# JIG_TEST_AUX_PIXYO-V10A.net
KiCad netlist of a schematic drawn in Altium Designer
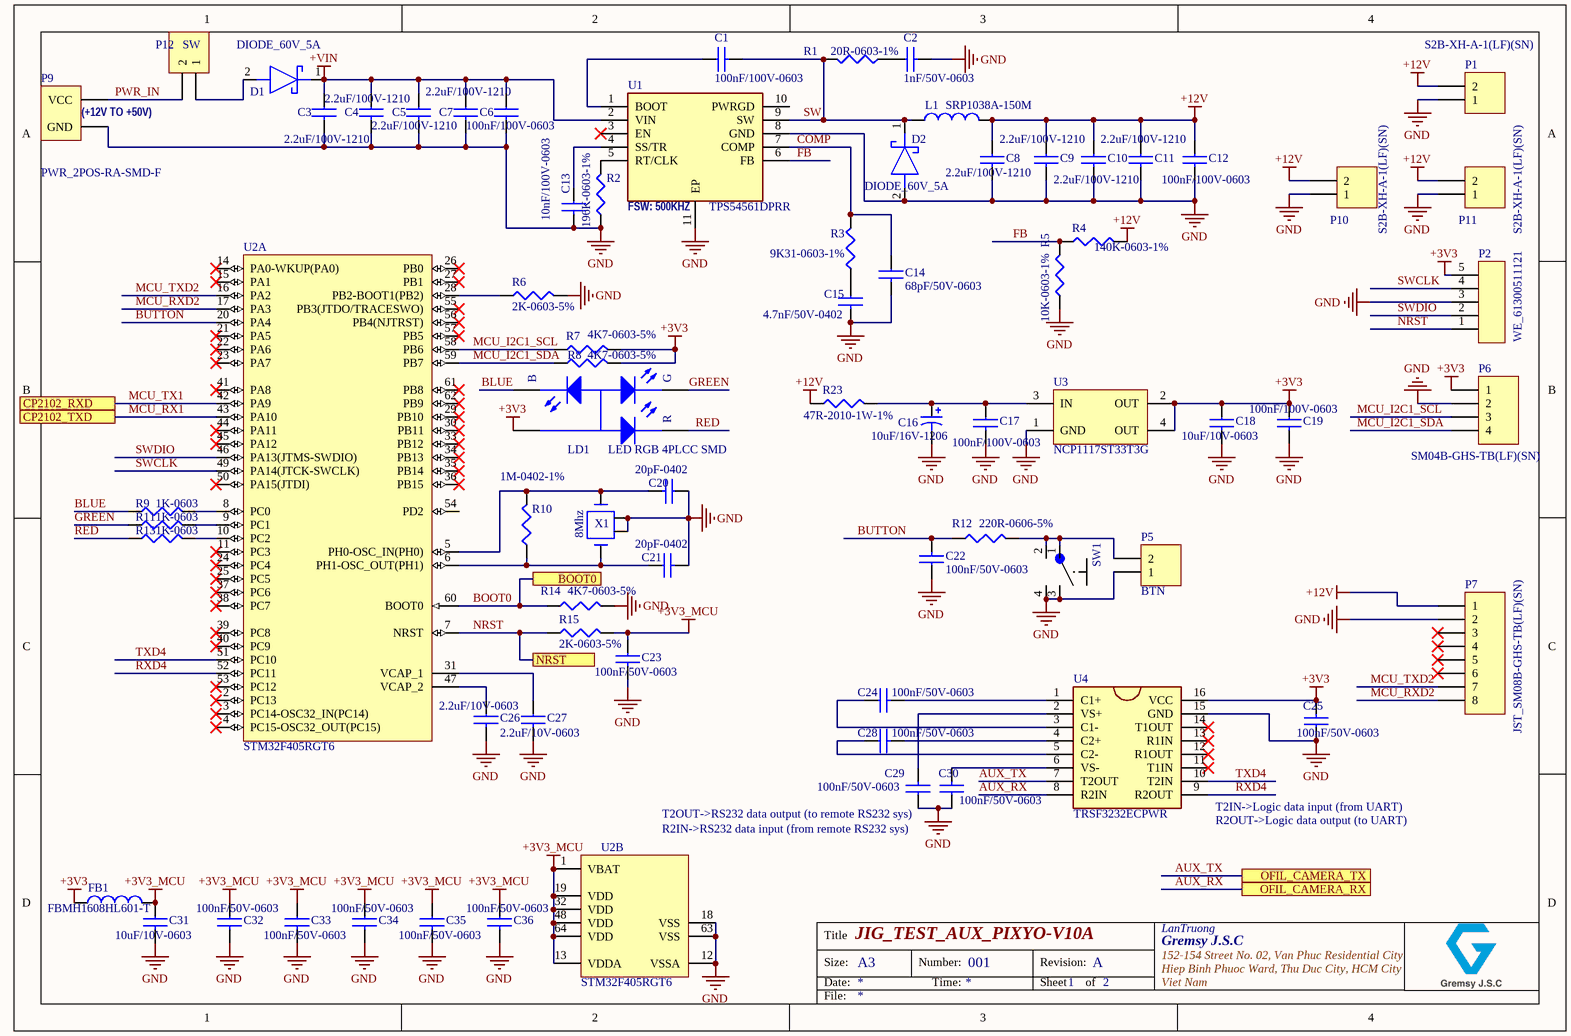
[diagram p0: JIG_TEST_AUX_PIXYO-V10A.SchDoc]

(export (version "E")
  (design (tool "Eeschema 10.0.6"))
  (components
    (comp (ref "C1")
      (value "100nF/100V-0603")
      (footprint "CAP0603")
      (description "CAP CER 0.1UF 100V X7R 0603")
      (fields (field (name "MANUFACTURER") "Yageo") (field (name "TOLERANCE") "±10%"))
      (libsource (lib "GremsyJSC") (part "CAP_100nF/100V-0603-10%"))
    )
    (comp (ref "C2")
      (value "1nF/50V-0603")
      (footprint "CAP0603")
      (description "CAP CER 1000PF 50V X7R 0603")
      (fields (field (name "MANUFACTURER") "Yageo") (field (name "TOLERANCE") "10%"))
      (libsource (lib "GremsyJSC") (part "CAP_1nF/50V-0603-10%"))
    )
    (comp (ref "C3")
      (value "2.2uF/100V-1210")
      (footprint "CAP1210")
      (description "CAP CER 2.2UF 100V X7R 1210")
      (fields (field (name "MANUFACTURER") "Taiyo Yuden") (field (name "TOLERANCE") "±10%"))
      (libsource (lib "GremsyJSC") (part "CAP_2.2uF/100V-1210-10%"))
    )
    (comp (ref "C4")
      (value "2.2uF/100V-1210")
      (footprint "CAP1210")
      (description "CAP CER 2.2UF 100V X7R 1210")
      (fields (field (name "MANUFACTURER") "Taiyo Yuden") (field (name "TOLERANCE") "±10%"))
      (libsource (lib "GremsyJSC") (part "CAP_2.2uF/100V-1210-10%"))
    )
    (comp (ref "C5")
      (value "2.2uF/100V-1210")
      (footprint "CAP1210")
      (description "CAP CER 2.2UF 100V X7R 1210")
      (fields (field (name "MANUFACTURER") "Taiyo Yuden") (field (name "TOLERANCE") "±10%"))
      (libsource (lib "GremsyJSC") (part "CAP_2.2uF/100V-1210-10%"))
    )
    (comp (ref "C6")
      (value "100nF/100V-0603")
      (footprint "CAP0603")
      (description "CAP CER 0.1UF 100V X7R 0603")
      (fields (field (name "MANUFACTURER") "Yageo") (field (name "TOLERANCE") "±10%"))
      (libsource (lib "GremsyJSC") (part "CAP_100nF/100V-0603-10%"))
    )
    (comp (ref "C7")
      (value "2.2uF/100V-1210")
      (footprint "CAP1210")
      (description "CAP CER 2.2UF 100V X7R 1210")
      (fields (field (name "MANUFACTURER") "Taiyo Yuden") (field (name "TOLERANCE") "±10%"))
      (libsource (lib "GremsyJSC") (part "CAP_2.2uF/100V-1210-10%"))
    )
    (comp (ref "C8")
      (value "2.2uF/100V-1210")
      (footprint "CAP1210")
      (description "CAP CER 2.2UF 100V X7R 1210")
      (fields (field (name "MANUFACTURER") "Taiyo Yuden") (field (name "TOLERANCE") "±10%"))
      (libsource (lib "GremsyJSC") (part "CAP_2.2uF/100V-1210-10%"))
    )
    (comp (ref "C9")
      (value "2.2uF/100V-1210")
      (footprint "CAP1210")
      (description "CAP CER 2.2UF 100V X7R 1210")
      (fields (field (name "MANUFACTURER") "Taiyo Yuden") (field (name "TOLERANCE") "±10%"))
      (libsource (lib "GremsyJSC") (part "CAP_2.2uF/100V-1210-10%"))
    )
    (comp (ref "C10")
      (value "2.2uF/100V-1210")
      (footprint "CAP1210")
      (description "CAP CER 2.2UF 100V X7R 1210")
      (fields (field (name "MANUFACTURER") "Taiyo Yuden") (field (name "TOLERANCE") "±10%"))
      (libsource (lib "GremsyJSC") (part "CAP_2.2uF/100V-1210-10%"))
    )
    (comp (ref "C11")
      (value "2.2uF/100V-1210")
      (footprint "CAP1210")
      (description "CAP CER 2.2UF 100V X7R 1210")
      (fields (field (name "MANUFACTURER") "Taiyo Yuden") (field (name "TOLERANCE") "±10%"))
      (libsource (lib "GremsyJSC") (part "CAP_2.2uF/100V-1210-10%"))
    )
    (comp (ref "C12")
      (value "100nF/100V-0603")
      (footprint "CAP0603")
      (description "CAP CER 0.1UF 100V X7R 0603")
      (fields (field (name "MANUFACTURER") "Yageo") (field (name "TOLERANCE") "±10%"))
      (libsource (lib "GremsyJSC") (part "CAP_100nF/100V-0603-10%"))
    )
    (comp (ref "C13")
      (value "10nF/100V-0603")
      (footprint "CAP0603")
      (description "CAP CER 10000PF 100V X7R 0603")
      (fields (field (name "MANUFACTURER") "Yageo") (field (name "TOLERANCE") "±10%"))
      (libsource (lib "GremsyJSC") (part "CAP_10nF/100V-0603-10%"))
    )
    (comp (ref "C14")
      (value "68pF/50V-0603")
      (footprint "CAP0603")
      (description "CAP CER 68PF 50V C0G/NPO 0603")
      (fields (field (name "MANUFACTURER") "Yageo") (field (name "TOLERANCE") "±5%"))
      (libsource (lib "GremsyJSC") (part "CAP_68pF/50V-0603-5%"))
    )
    (comp (ref "C15")
      (value "4.7nF/50V-0402")
      (footprint "CAP0402")
      (description "CAP CER 4700PF 50V X7R 0402")
      (fields (field (name "TOLERANCE") "5%"))
      (libsource (lib "GremsyJSC") (part "CAP_4.7nF/50V-0402-5%"))
    )
    (comp (ref "C16")
      (value "10uF/16V-1206")
      (footprint "CAP1206_TANTALUM_YELLOW")
      (description "CAP TANT 10UF 16V 10% 1206")
      (fields (field (name "TOLERANCE") "±10%"))
      (libsource (lib "GremsyJSC") (part "CAP_10uF/16V-1206-10%"))
    )
    (comp (ref "C17")
      (value "100nF/100V-0603")
      (footprint "CAP0603")
      (description "CAP CER 0.1UF 100V X7R 0603")
      (fields (field (name "MANUFACTURER") "Yageo") (field (name "TOLERANCE") "±10%"))
      (libsource (lib "GremsyJSC") (part "CAP_100nF/100V-0603-10%"))
    )
    (comp (ref "C18")
      (value "10uF/10V-0603")
      (footprint "CAP0603")
      (description "CAP CER 10UF 10V X5R 0603")
      (fields (field (name "TOLERANCE") "±10%"))
      (libsource (lib "GremsyJSC") (part "CAP_10uF/10V-0603-10%"))
    )
    (comp (ref "C19")
      (value "100nF/100V-0603")
      (footprint "CAP0603")
      (description "CAP CER 0.1UF 100V X7R 0603")
      (fields (field (name "MANUFACTURER") "Yageo") (field (name "TOLERANCE") "±10%"))
      (libsource (lib "GremsyJSC") (part "CAP_100nF/100V-0603-10%"))
    )
    (comp (ref "C20")
      (value "20pF-0402")
      (footprint "CAP0402")
      (description "CAP CER 20PF 50V C0G/NP0 0402")
      (fields (field (name "TOLERANCE") "1%"))
      (libsource (lib "GremsyJSC") (part "CAP_20pF/50V-0402-1%"))
    )
    (comp (ref "C21")
      (value "20pF-0402")
      (footprint "CAP0402")
      (description "CAP CER 20PF 50V C0G/NP0 0402")
      (fields (field (name "TOLERANCE") "1%"))
      (libsource (lib "GremsyJSC") (part "CAP_20pF/50V-0402-1%"))
    )
    (comp (ref "C22")
      (value "100nF/50V-0603")
      (footprint "CAP0603")
      (description "CAP CER 0.1UF 50V X7R 0603")
      (fields (field (name "TOLERANCE") "±10%"))
      (libsource (lib "GremsyJSC") (part "CAP_100nF/50V-0603-10%"))
    )
    (comp (ref "C23")
      (value "100nF/50V-0603")
      (footprint "CAP0603")
      (description "CAP CER 0.1UF 50V X7R 0603")
      (fields (field (name "TOLERANCE") "±10%"))
      (libsource (lib "GremsyJSC") (part "CAP_100nF/50V-0603-10%"))
    )
    (comp (ref "C24")
      (value "100nF/50V-0603")
      (footprint "CAP0603")
      (description "CAP CER 0.1UF 50V X7R 0603")
      (fields (field (name "TOLERANCE") "±10%"))
      (libsource (lib "GremsyJSC") (part "CAP_100nF/50V-0603-10%"))
    )
    (comp (ref "C25")
      (value "100nF/50V-0603")
      (footprint "CAP0603")
      (description "CAP CER 0.1UF 50V X7R 0603")
      (fields (field (name "TOLERANCE") "±10%"))
      (libsource (lib "GremsyJSC") (part "CAP_100nF/50V-0603-10%"))
    )
    (comp (ref "C26")
      (value "2.2uF/10V-0603")
      (footprint "CAP0603")
      (description "CAP CER 2.2UF 10V X7R 0603")
      (fields (field (name "TOLERANCE") "±10%"))
      (libsource (lib "GremsyJSC") (part "CAP_2.2uF/10V-0603-10%"))
    )
    (comp (ref "C27")
      (value "2.2uF/10V-0603")
      (footprint "CAP0603")
      (description "CAP CER 2.2UF 10V X7R 0603")
      (fields (field (name "TOLERANCE") "±10%"))
      (libsource (lib "GremsyJSC") (part "CAP_2.2uF/10V-0603-10%"))
    )
    (comp (ref "C28")
      (value "100nF/50V-0603")
      (footprint "CAP0603")
      (description "CAP CER 0.1UF 50V X7R 0603")
      (fields (field (name "TOLERANCE") "±10%"))
      (libsource (lib "GremsyJSC") (part "CAP_100nF/50V-0603-10%"))
    )
    (comp (ref "C29")
      (value "100nF/50V-0603")
      (footprint "CAP0603")
      (description "CAP CER 0.1UF 50V X7R 0603")
      (fields (field (name "TOLERANCE") "±10%"))
      (libsource (lib "GremsyJSC") (part "CAP_100nF/50V-0603-10%"))
    )
    (comp (ref "C30")
      (value "100nF/50V-0603")
      (footprint "CAP0603")
      (description "CAP CER 0.1UF 50V X7R 0603")
      (fields (field (name "TOLERANCE") "±10%"))
      (libsource (lib "GremsyJSC") (part "CAP_100nF/50V-0603-10%"))
    )
    (comp (ref "C31")
      (value "10uF/10V-0603")
      (footprint "CAP0603")
      (description "CAP CER 10UF 10V X5R 0603")
      (fields (field (name "TOLERANCE") "±10%"))
      (libsource (lib "GremsyJSC") (part "CAP_10uF/10V-0603-10%"))
    )
    (comp (ref "C32")
      (value "100nF/50V-0603")
      (footprint "CAP0603")
      (description "CAP CER 0.1UF 50V X7R 0603")
      (fields (field (name "TOLERANCE") "±10%"))
      (libsource (lib "GremsyJSC") (part "CAP_100nF/50V-0603-10%"))
    )
    (comp (ref "C33")
      (value "100nF/50V-0603")
      (footprint "CAP0603")
      (description "CAP CER 0.1UF 50V X7R 0603")
      (fields (field (name "TOLERANCE") "±10%"))
      (libsource (lib "GremsyJSC") (part "CAP_100nF/50V-0603-10%"))
    )
    (comp (ref "C34")
      (value "100nF/50V-0603")
      (footprint "CAP0603")
      (description "CAP CER 0.1UF 50V X7R 0603")
      (fields (field (name "TOLERANCE") "±10%"))
      (libsource (lib "GremsyJSC") (part "CAP_100nF/50V-0603-10%"))
    )
    (comp (ref "C35")
      (value "100nF/50V-0603")
      (footprint "CAP0603")
      (description "CAP CER 0.1UF 50V X7R 0603")
      (fields (field (name "TOLERANCE") "±10%"))
      (libsource (lib "GremsyJSC") (part "CAP_100nF/50V-0603-10%"))
    )
    (comp (ref "C36")
      (value "100nF/50V-0603")
      (footprint "CAP0603")
      (description "CAP CER 0.1UF 50V X7R 0603")
      (fields (field (name "TOLERANCE") "±10%"))
      (libsource (lib "GremsyJSC") (part "CAP_100nF/50V-0603-10%"))
    )
    (comp (ref "D1")
      (value "DIODE_60V_5A")
      (footprint "SODFL4725X105N")
      (description "Schottky Diode")
      (fields
        (field (name "MOUSER PART NUMBER") "755-RB088LAM-60TFTR")
        (field (name "MANUFACTURER PART NUMBER") "RB088LAM-60TFTR")
      )
      (libsource (lib "GremsyJSC") (part "DIODE-SCHOTTKY_RB088LAM-60TFTR"))
    )
    (comp (ref "D2")
      (value "DIODE_60V_5A")
      (footprint "SODFL4725X105N")
      (description "Schottky Diode")
      (fields
        (field (name "MOUSER PART NUMBER") "755-RB088LAM-60TFTR")
        (field (name "MANUFACTURER PART NUMBER") "RB088LAM-60TFTR")
      )
      (libsource (lib "GremsyJSC") (part "DIODE-SCHOTTKY_RB088LAM-60TFTR"))
    )
    (comp (ref "FB1")
      (value "FBMH1608HL601-T")
      (footprint "INDC0603")
      (description "FERRITE BEAD 600 OHM 0603 1LN")
      (fields (field (name "MANUFACTURER") "Taiyo Yuden"))
      (libsource (lib "GremsyJSC") (part "FB-0603_FBMH1608HL601-T"))
    )
    (comp (ref "L1")
      (value "SRP1038A-150M")
      (footprint "INDC_SRP1038A-150M")
      (description "BOURNS   SRP1038A-150M   INDUCTOR, SHIELDED, 15UH, 20%, 6.25A")
      (fields (field (name "MANUFACTURER") "Bourns") (field (name "TOLERANCE") "20%"))
      (libsource (lib "GremsyCo_8_18") (part "IND_SRP1038A-150M"))
    )
    (comp (ref "LD1")
      (value "LED RGB 4PLCC SMD")
      (footprint "LED RGB 4PLCC SMD")
      (libsource (lib "GremsyJSC") (part "LED-RGB_4PLCC_SMD"))
    )
    (comp (ref "P1")
      (value "S2B-XH-A-1(LF)(SN)")
      (footprint "XH2.54 2P 2pin XH-2AW Right Angle")
      (description "WTB-XH_2POS-P2.54-RA-TH")
      (libsource (lib "GremsyJSC") (part "CON-JST_S2B-XH-A-1(LF)(SN)"))
    )
    (comp (ref "P2")
      (value "WE_61300511121")
      (footprint "HDR_1x5_2m54")
      (description "HEADER HDR 1X5-P2.54-ST-TH-MALE")
      (libsource (lib "GremsyJSC") (part "CON-WE_61300511121_DUPLICATE"))
    )
    (comp (ref "P5")
      (value "BTN")
      (footprint "JST_SM02B-GHS-TB(LF)(SN)")
      (description "WTB-GH_2POS-P1.25-RA-SMD")
      (fields (field (name "MANUFACTURER") "JST Sales America Inc."))
      (libsource (lib "GremsyJSC") (part "CON-JST_SM02B-GHS-TB(LF)(SN)"))
    )
    (comp (ref "P6")
      (value "SM04B-GHS-TB(LF)(SN)")
      (footprint "JST_SM04B-GHS-TB(LF)(SN)")
      (description "WTB-GH_4POS-P1.25-RA-SMD")
      (fields (field (name "MANUFACTURER") "JST Sales America Inc."))
      (libsource (lib "GremsyJSC") (part "CON-JST_SM04B-GHS-TB(LF)(SN)"))
    )
    (comp (ref "P7")
      (value "JST_SM08B-GHS-TB(LF)(SN)")
      (footprint "JST_SM08B-GHS-TB(LF)(SN)")
      (description "WTB-GH_8POS-P1.25-RA-SMD")
      (fields (field (name "MANUFACTURER") "JST Sales America Inc."))
      (libsource (lib "GremsyJSC") (part "CON-JST_SM08B-GHS-TB(LF)(SN)"))
    )
    (comp (ref "P9")
      (value "PWR_2POS-RA-SMD-F")
      (footprint "DC-050")
      (description "PWR DC CONNECTOR, NONAME, FEMALE, 5.5MM")
      (libsource (lib "GremsyJSC") (part "CON-NONAME_2POS-RA-SMD-F"))
    )
    (comp (ref "P10")
      (value "S2B-XH-A-1(LF)(SN)")
      (footprint "XH2.54 2P 2pin XH-2AW Right Angle")
      (description "WTB-XH_2POS-P2.54-RA-TH")
      (libsource (lib "GremsyJSC") (part "CON-JST_S2B-XH-A-1(LF)(SN)"))
    )
    (comp (ref "P11")
      (value "S2B-XH-A-1(LF)(SN)")
      (footprint "XH2.54 2P 2pin XH-2AW Right Angle")
      (description "WTB-XH_2POS-P2.54-RA-TH")
      (libsource (lib "GremsyJSC") (part "CON-JST_S2B-XH-A-1(LF)(SN)"))
    )
    (comp (ref "P12")
      (value "SW")
      (footprint "GremsyJSC:JST_B2B-XH-A(LF)(SN)")
      (description "WTB-XH_2POS-P2.54-ST-TH")
      (libsource (lib "GremsyJSC") (part "CON-JST_B2B-XH-A(LF)(SN)"))
    )
    (comp (ref "R1")
      (value "20R-0603-1%")
      (footprint "RES0603")
      (description "RES 20 OHM 1% 1/10W 0603")
      (fields (field (name "MANUFACTURER") "Yageo") (field (name "TOLERANCE") "1%"))
      (libsource (lib "GremsyJSC") (part "RES_20R-0603-1%"))
    )
    (comp (ref "R2")
      (value "196K-0603-1%")
      (footprint "RES0603")
      (description "RES 196K OHM 1% 1/10W 0603")
      (fields (field (name "MANUFACTURER") "Yageo") (field (name "TOLERANCE") "±1%"))
      (libsource (lib "GremsyJSC") (part "RES_196K-0603-1%"))
    )
    (comp (ref "R3")
      (value "9K31-0603-1%")
      (footprint "RES0603")
      (description "RES 9.31K OHM 1% 1/10W 0603")
      (fields (field (name "MANUFACTURER") "Yageo") (field (name "TOLERANCE") "±1%"))
      (libsource (lib "GremsyJSC") (part "RES_9K31-0603-1%"))
    )
    (comp (ref "R4")
      (value "140K-0603-1%")
      (footprint "RES0603")
      (description "RES SMD 140K OHM 1% 1/10W 0603")
      (fields (field (name "MANUFACTURER") "Yageo") (field (name "TOLERANCE") "±1%"))
      (libsource (lib "GremsyJSC") (part "RES_140K-0603-1%"))
    )
    (comp (ref "R5")
      (value "10K-0603-1%")
      (footprint "RES0603")
      (description "RES 10K OHM 1% 1/10W 0603")
      (fields (field (name "MANUFACTURER") "Yageo") (field (name "TOLERANCE") "±1%"))
      (libsource (lib "GremsyJSC") (part "RES_10K-0603-1%"))
    )
    (comp (ref "R6")
      (value "2K-0603-5%")
      (footprint "RES0603")
      (description "RES 2K OHM 5% 1/10W 0603")
      (fields (field (name "TOLERANCE") "±5%"))
      (libsource (lib "GremsyJSC") (part "RES_2K-0603-5%"))
    )
    (comp (ref "R7")
      (value "4K7-0603-5%")
      (footprint "RES0603")
      (description "RES 4.7K OHM 5% 1/10W 0603")
      (fields (field (name "MANUFACTURER") "Yageo") (field (name "TOLERANCE") "±5%"))
      (libsource (lib "GremsyJSC") (part "RES_4K7-0603-5%"))
    )
    (comp (ref "R8")
      (value "4K7-0603-5%")
      (footprint "RES0603")
      (description "RES 4.7K OHM 5% 1/10W 0603")
      (fields (field (name "MANUFACTURER") "Yageo") (field (name "TOLERANCE") "±5%"))
      (libsource (lib "GremsyJSC") (part "RES_4K7-0603-5%"))
    )
    (comp (ref "R9")
      (value "1K-0603")
      (footprint "RES0603")
      (description "RES 1K OHM 5% 1/10W 0603")
      (fields (field (name "TOLERANCE") "±5%"))
      (libsource (lib "GremsyJSC") (part "RES_1K-0603-5%"))
    )
    (comp (ref "R10")
      (value "1M-0402-1%")
      (footprint "RES0402")
      (description "RES 1M OHM 1% 1/16W 0402")
      (fields (field (name "TOLERANCE") "1%"))
      (libsource (lib "GremsyJSC") (part "RES_1M_0402_1%"))
    )
    (comp (ref "R11")
      (value "1K-0603")
      (footprint "RES0603")
      (description "RES 1K OHM 5% 1/10W 0603")
      (fields (field (name "TOLERANCE") "±5%"))
      (libsource (lib "GremsyJSC") (part "RES_1K-0603-5%"))
    )
    (comp (ref "R12")
      (value "220R-0606-5%")
      (footprint "RES0603")
      (description "RES 220 OHM 5% 1/10W 0603")
      (fields (field (name "TOLERANCE") "±5%"))
      (libsource (lib "GremsyJSC") (part "RES_220R-0606-5%"))
    )
    (comp (ref "R13")
      (value "1K-0603")
      (footprint "RES0603")
      (description "RES 1K OHM 5% 1/10W 0603")
      (fields (field (name "TOLERANCE") "±5%"))
      (libsource (lib "GremsyJSC") (part "RES_1K-0603-5%"))
    )
    (comp (ref "R14")
      (value "4K7-0603-5%")
      (footprint "RES0603")
      (description "RES 4.7K OHM 5% 1/10W 0603")
      (fields (field (name "MANUFACTURER") "Yageo") (field (name "TOLERANCE") "±5%"))
      (libsource (lib "GremsyJSC") (part "RES_4K7-0603-5%"))
    )
    (comp (ref "R15")
      (value "2K-0603-5%")
      (footprint "RES0603")
      (description "RES 2K OHM 5% 1/10W 0603")
      (fields (field (name "TOLERANCE") "±5%"))
      (libsource (lib "GremsyJSC") (part "RES_2K-0603-5%"))
    )
    (comp (ref "R23")
      (value "47R-2010-1W-1%")
      (footprint "RES2010")
      (description "RES SMD 47 OHM 1% 1W 2010")
      (fields (field (name "MANUFACTURER") "Stackpole Electronics") (field (name "TOLERANCE") "1%"))
      (libsource (lib "GremsyJSC") (part "RES_47R-2010-1W-1%"))
    )
    (comp (ref "SW1")
      (value "SW_FSM14JLH")
      (footprint "Pushbutton 6x6mm")
      (description "SWITCH TACTILE SPST-NO 0.05A 24V, STRAIGHT, SMD")
      (fields (field (name "MF") "TE Connectivity"))
      (libsource (lib "GremsyJSC") (part "SW-TACTILE_FSM14JLH-ST-TH"))
    )
    (comp (ref "U1")
      (value "TPS54561DPRR")
      (footprint "SON80P400X400X80-11N-D")
      (description "Buck Switching Regulator IC Positive Adjustable 0.8V 1 Output 5A 10-WDFN Exposed Pad")
      (fields (field (name "MOUSER2 PART NUMBER") "595-TPS54561DPRR"))
      (libsource (lib "GremsyJSC") (part "IC-PMIC-TI_TPS54561DPRR"))
    )
    (comp (ref "U2")
      (value "STM32F405RGT6")
      (footprint "LQFP64_L")
      (fields (field (name "MANUFACTURER") "STMicroelectronics"))
      (libsource (lib "GremsyJSC") (part "IC-MCU_STM32F405RGT6"))
    )
    (comp (ref "U3")
      (value "NCP1117ST33T3G")
      (footprint "SOT223-4M")
      (description "IC REG LINEAR 3.3V 1A SOT223, Linear Voltage Regulator IC Positive Fixed 1 Output 1A SOT-223")
      (libsource (lib "GremsyJSC") (part "IC-PMIC-ON_NCP1117ST33T3G"))
    )
    (comp (ref "U4")
      (value "TRSF3232ECPWR")
      (footprint "TSSOP-16")
      (description "IC TRANSCEIVER FULL 2/2 16TSSOP")
      (libsource (lib "GremsyJSC") (part "IC-INFA-TI_TRSF3232ECPWR"))
    )
    (comp (ref "X1")
      (value "8Mhz")
      (footprint "XTAL_SMD5032")
      (description "CRYSTAL 8.0000MHZ 18PF SMD")
      (fields (field (name "MANUFACTURER PART NUMBER") "7B-8.000MAHJ-T"))
      (libsource (lib "GremsyJSC") (part "XTAL-8MHz_7B-8.000MAAJ-T"))
    )
  )
  (nets
    (net (code "1") (name "+3V3") (class "Default")
      (node (ref "C18") (pin "1") (pinfunction "1_1") (pintype "passive"))
      (node (ref "C19") (pin "1") (pinfunction "1_1") (pintype "passive"))
      (node (ref "C25") (pin "2") (pinfunction "2_2") (pintype "passive"))
      (node (ref "FB1") (pin "1") (pinfunction "1_1") (pintype "passive"))
      (node (ref "LD1") (pin "2") (pinfunction "A_2") (pintype "passive"))
      (node (ref "P2") (pin "5") (pinfunction "5_5") (pintype "passive"))
      (node (ref "P6") (pin "1") (pinfunction "1_1") (pintype "passive"))
      (node (ref "R7") (pin "2") (pinfunction "2_2") (pintype "passive"))
      (node (ref "R8") (pin "2") (pinfunction "2_2") (pintype "passive"))
      (node (ref "U3") (pin "2") (pinfunction "OUT_2") (pintype "passive"))
      (node (ref "U3") (pin "4") (pinfunction "OUT_4") (pintype "passive"))
      (node (ref "U4") (pin "16") (pinfunction "VCC_16") (pintype "passive"))
    )
    (net (code "2") (name "+3V3_MCU") (class "Default")
      (node (ref "C23") (pin "1") (pinfunction "1_1") (pintype "passive"))
      (node (ref "C31") (pin "1") (pinfunction "1_1") (pintype "passive"))
      (node (ref "C32") (pin "1") (pinfunction "1_1") (pintype "passive"))
      (node (ref "C33") (pin "1") (pinfunction "1_1") (pintype "passive"))
      (node (ref "C34") (pin "1") (pinfunction "1_1") (pintype "passive"))
      (node (ref "C35") (pin "1") (pinfunction "1_1") (pintype "passive"))
      (node (ref "C36") (pin "1") (pinfunction "1_1") (pintype "passive"))
      (node (ref "FB1") (pin "2") (pinfunction "2_2") (pintype "passive"))
      (node (ref "R15") (pin "2") (pinfunction "2_2") (pintype "passive"))
      (node (ref "U2") (pin "1") (pinfunction "VBAT_1") (pintype "power_in"))
      (node (ref "U2") (pin "13") (pinfunction "VDDA_13") (pintype "power_in"))
      (node (ref "U2") (pin "19") (pinfunction "VDD_19") (pintype "power_in"))
      (node (ref "U2") (pin "32") (pinfunction "VDD_32") (pintype "power_in"))
      (node (ref "U2") (pin "48") (pinfunction "VDD_48") (pintype "power_in"))
      (node (ref "U2") (pin "64") (pinfunction "VDD_64") (pintype "power_in"))
    )
    (net (code "3") (name "+12V") (class "Default")
      (node (ref "C10") (pin "1") (pinfunction "1_1") (pintype "passive"))
      (node (ref "C11") (pin "1") (pinfunction "1_1") (pintype "passive"))
      (node (ref "C12") (pin "1") (pinfunction "1_1") (pintype "passive"))
      (node (ref "C8") (pin "1") (pinfunction "1_1") (pintype "passive"))
      (node (ref "C9") (pin "1") (pinfunction "1_1") (pintype "passive"))
      (node (ref "L1") (pin "2") (pinfunction "2_2") (pintype "passive"))
      (node (ref "P1") (pin "2") (pinfunction "2_2") (pintype "passive"))
      (node (ref "P10") (pin "2") (pinfunction "2_2") (pintype "passive"))
      (node (ref "P11") (pin "2") (pinfunction "2_2") (pintype "passive"))
      (node (ref "P7") (pin "1") (pinfunction "1_1") (pintype "passive"))
      (node (ref "R23") (pin "1") (pinfunction "1_1") (pintype "passive"))
      (node (ref "R4") (pin "2") (pinfunction "2_2") (pintype "passive"))
    )
    (net (code "4") (name "+VIN") (class "Default")
      (node (ref "C3") (pin "1") (pinfunction "1_1") (pintype "passive"))
      (node (ref "C4") (pin "1") (pinfunction "1_1") (pintype "passive"))
      (node (ref "C5") (pin "1") (pinfunction "1_1") (pintype "passive"))
      (node (ref "C6") (pin "1") (pinfunction "1_1") (pintype "passive"))
      (node (ref "C7") (pin "1") (pinfunction "1_1") (pintype "passive"))
      (node (ref "D1") (pin "1") (pinfunction "K_1") (pintype "passive"))
      (node (ref "U1") (pin "2") (pinfunction "VIN_2") (pintype "passive"))
    )
    (net (code "5") (name "/AUX_RX") (class "Default")
      (node (ref "U4") (pin "8") (pinfunction "R2IN_8") (pintype "passive"))
    )
    (net (code "6") (name "/AUX_TX") (class "Default")
      (node (ref "U4") (pin "7") (pinfunction "T2OUT_7") (pintype "passive"))
    )
    (net (code "7") (name "/BLUE") (class "Default")
      (node (ref "LD1") (pin "3") (pinfunction "B_3") (pintype "passive"))
      (node (ref "R9") (pin "1") (pinfunction "1_1") (pintype "passive"))
    )
    (net (code "8") (name "/BOOT0") (class "Default")
      (node (ref "R14") (pin "1") (pinfunction "1_1") (pintype "passive"))
      (node (ref "U2") (pin "60") (pinfunction "BOOT0_60") (pintype "input"))
    )
    (net (code "9") (name "/BUTTON") (class "Default")
      (node (ref "C22") (pin "2") (pinfunction "2_2") (pintype "passive"))
      (node (ref "R12") (pin "1") (pinfunction "1_1") (pintype "passive"))
      (node (ref "U2") (pin "20") (pinfunction "PA4_20") (pintype "bidirectional"))
    )
    (net (code "10") (name "/COMP") (class "Default")
      (node (ref "C14") (pin "1") (pinfunction "1_1") (pintype "passive"))
      (node (ref "R3") (pin "2") (pinfunction "2_2") (pintype "passive"))
      (node (ref "U1") (pin "7") (pinfunction "COMP_7") (pintype "passive"))
    )
    (net (code "11") (name "/FB") (class "Default")
      (node (ref "R4") (pin "1") (pinfunction "1_1") (pintype "passive"))
      (node (ref "R5") (pin "2") (pinfunction "2_2") (pintype "passive"))
      (node (ref "U1") (pin "6") (pinfunction "FB_6") (pintype "passive"))
    )
    (net (code "12") (name "/GREEN") (class "Default")
      (node (ref "LD1") (pin "4") (pinfunction "G_4") (pintype "passive"))
      (node (ref "R11") (pin "1") (pinfunction "1_1") (pintype "passive"))
    )
    (net (code "13") (name "/MCU_I2C1_SCL") (class "Default")
      (node (ref "P6") (pin "3") (pinfunction "3_3") (pintype "passive"))
      (node (ref "R7") (pin "1") (pinfunction "1_1") (pintype "passive"))
      (node (ref "U2") (pin "58") (pinfunction "PB6_58") (pintype "bidirectional"))
    )
    (net (code "14") (name "/MCU_I2C1_SDA") (class "Default")
      (node (ref "P6") (pin "4") (pinfunction "4_4") (pintype "passive"))
      (node (ref "R8") (pin "1") (pinfunction "1_1") (pintype "passive"))
      (node (ref "U2") (pin "59") (pinfunction "PB7_59") (pintype "bidirectional"))
    )
    (net (code "15") (name "/MCU_RX1") (class "Default")
      (node (ref "U2") (pin "43") (pinfunction "PA10_43") (pintype "bidirectional"))
    )
    (net (code "16") (name "/MCU_RXD2") (class "Default")
      (node (ref "P7") (pin "8") (pinfunction "8_8") (pintype "passive"))
      (node (ref "U2") (pin "17") (pinfunction "PA3_17") (pintype "bidirectional"))
    )
    (net (code "17") (name "/MCU_TX1") (class "Default")
      (node (ref "U2") (pin "42") (pinfunction "PA9_42") (pintype "bidirectional"))
    )
    (net (code "18") (name "/MCU_TXD2") (class "Default")
      (node (ref "P7") (pin "7") (pinfunction "7_7") (pintype "passive"))
      (node (ref "U2") (pin "16") (pinfunction "PA2_16") (pintype "bidirectional"))
    )
    (net (code "19") (name "/NRST") (class "Default")
      (node (ref "P2") (pin "1") (pinfunction "1_1") (pintype "passive"))
      (node (ref "R15") (pin "1") (pinfunction "1_1") (pintype "passive"))
      (node (ref "U2") (pin "7") (pinfunction "NRST_7") (pintype "bidirectional"))
    )
    (net (code "20") (name "/PWR_IN") (class "Default")
      (node (ref "P12") (pin "2") (pinfunction "2_2") (pintype "passive"))
      (node (ref "P9") (pin "1") (pinfunction "VCC_1") (pintype "passive"))
    )
    (net (code "21") (name "/RED") (class "Default")
      (node (ref "LD1") (pin "1") (pinfunction "R_1") (pintype "passive"))
      (node (ref "R13") (pin "1") (pinfunction "1_1") (pintype "passive"))
    )
    (net (code "22") (name "/RXD4") (class "Default")
      (node (ref "U2") (pin "52") (pinfunction "PC11_52") (pintype "bidirectional"))
      (node (ref "U4") (pin "9") (pinfunction "R2OUT_9") (pintype "passive"))
    )
    (net (code "23") (name "/SW") (class "Default")
      (node (ref "C1") (pin "2") (pinfunction "2_2") (pintype "passive"))
      (node (ref "D2") (pin "1") (pinfunction "K_1") (pintype "passive"))
      (node (ref "L1") (pin "1") (pinfunction "1_1") (pintype "passive"))
      (node (ref "R1") (pin "2") (pinfunction "2_2") (pintype "passive"))
      (node (ref "U1") (pin "9") (pinfunction "SW_9") (pintype "passive"))
    )
    (net (code "24") (name "/SWCLK") (class "Default")
      (node (ref "P2") (pin "4") (pinfunction "4_4") (pintype "passive"))
      (node (ref "U2") (pin "49") (pinfunction "PA14(JTCK-SWCLK)_49") (pintype "bidirectional"))
    )
    (net (code "25") (name "/SWDIO") (class "Default")
      (node (ref "P2") (pin "2") (pinfunction "2_2") (pintype "passive"))
      (node (ref "U2") (pin "46") (pinfunction "PA13(JTMS-SWDIO)_46") (pintype "bidirectional"))
    )
    (net (code "26") (name "/TXD4") (class "Default")
      (node (ref "U2") (pin "51") (pinfunction "PC10_51") (pintype "bidirectional"))
      (node (ref "U4") (pin "10") (pinfunction "T2IN_10") (pintype "passive"))
    )
    (net (code "27") (name "GND") (class "Default")
      (node (ref "C10") (pin "2") (pinfunction "2_2") (pintype "passive"))
      (node (ref "C11") (pin "2") (pinfunction "2_2") (pintype "passive"))
      (node (ref "C12") (pin "2") (pinfunction "2_2") (pintype "passive"))
      (node (ref "C13") (pin "2") (pinfunction "2_2") (pintype "passive"))
      (node (ref "C14") (pin "2") (pinfunction "2_2") (pintype "passive"))
      (node (ref "C15") (pin "2") (pinfunction "2_2") (pintype "passive"))
      (node (ref "C16") (pin "2") (pinfunction "2_2") (pintype "passive"))
      (node (ref "C17") (pin "2") (pinfunction "2_2") (pintype "passive"))
      (node (ref "C18") (pin "2") (pinfunction "2_2") (pintype "passive"))
      (node (ref "C19") (pin "2") (pinfunction "2_2") (pintype "passive"))
      (node (ref "C2") (pin "2") (pinfunction "2_2") (pintype "passive"))
      (node (ref "C20") (pin "1") (pinfunction "1_1") (pintype "passive"))
      (node (ref "C21") (pin "2") (pinfunction "2_2") (pintype "passive"))
      (node (ref "C22") (pin "1") (pinfunction "1_1") (pintype "passive"))
      (node (ref "C23") (pin "2") (pinfunction "2_2") (pintype "passive"))
      (node (ref "C25") (pin "1") (pinfunction "1_1") (pintype "passive"))
      (node (ref "C26") (pin "2") (pinfunction "2_2") (pintype "passive"))
      (node (ref "C27") (pin "2") (pinfunction "2_2") (pintype "passive"))
      (node (ref "C29") (pin "1") (pinfunction "1_1") (pintype "passive"))
      (node (ref "C3") (pin "2") (pinfunction "2_2") (pintype "passive"))
      (node (ref "C30") (pin "1") (pinfunction "1_1") (pintype "passive"))
      (node (ref "C31") (pin "2") (pinfunction "2_2") (pintype "passive"))
      (node (ref "C32") (pin "2") (pinfunction "2_2") (pintype "passive"))
      (node (ref "C33") (pin "2") (pinfunction "2_2") (pintype "passive"))
      (node (ref "C34") (pin "2") (pinfunction "2_2") (pintype "passive"))
      (node (ref "C35") (pin "2") (pinfunction "2_2") (pintype "passive"))
      (node (ref "C36") (pin "2") (pinfunction "2_2") (pintype "passive"))
      (node (ref "C4") (pin "2") (pinfunction "2_2") (pintype "passive"))
      (node (ref "C5") (pin "2") (pinfunction "2_2") (pintype "passive"))
      (node (ref "C6") (pin "2") (pinfunction "2_2") (pintype "passive"))
      (node (ref "C7") (pin "2") (pinfunction "2_2") (pintype "passive"))
      (node (ref "C8") (pin "2") (pinfunction "2_2") (pintype "passive"))
      (node (ref "C9") (pin "2") (pinfunction "2_2") (pintype "passive"))
      (node (ref "D2") (pin "2") (pinfunction "A_2") (pintype "passive"))
      (node (ref "P1") (pin "1") (pinfunction "1_1") (pintype "passive"))
      (node (ref "P10") (pin "1") (pinfunction "1_1") (pintype "passive"))
      (node (ref "P11") (pin "1") (pinfunction "1_1") (pintype "passive"))
      (node (ref "P2") (pin "3") (pinfunction "3_3") (pintype "passive"))
      (node (ref "P5") (pin "1") (pinfunction "1_1") (pintype "passive"))
      (node (ref "P6") (pin "2") (pinfunction "2_2") (pintype "passive"))
      (node (ref "P7") (pin "2") (pinfunction "2_2") (pintype "passive"))
      (node (ref "P9") (pin "2") (pinfunction "GND_2") (pintype "passive"))
      (node (ref "R14") (pin "2") (pinfunction "2_2") (pintype "passive"))
      (node (ref "R2") (pin "1") (pinfunction "1_1") (pintype "passive"))
      (node (ref "R5") (pin "1") (pinfunction "1_1") (pintype "passive"))
      (node (ref "R6") (pin "2") (pinfunction "2_2") (pintype "passive"))
      (node (ref "SW1") (pin "3") (pinfunction "2_3") (pintype "passive"))
      (node (ref "SW1") (pin "4") (pinfunction "2_4") (pintype "passive"))
      (node (ref "U1") (pin "11") (pinfunction "EP_11") (pintype "passive"))
      (node (ref "U1") (pin "8") (pinfunction "GND_8") (pintype "passive"))
      (node (ref "U2") (pin "12") (pinfunction "VSSA_12") (pintype "power_in"))
      (node (ref "U2") (pin "18") (pinfunction "VSS_18") (pintype "power_in"))
      (node (ref "U2") (pin "63") (pinfunction "VSS_63") (pintype "power_in"))
      (node (ref "U3") (pin "1") (pinfunction "GND_1") (pintype "power_in"))
      (node (ref "U4") (pin "15") (pinfunction "GND_15") (pintype "passive"))
      (node (ref "X1") (pin "2") (pinfunction "GND_2") (pintype "passive"))
      (node (ref "X1") (pin "4") (pinfunction "GND_4") (pintype "passive"))
    )
    (net (code "28") (name "Net-(C2-Pad1)") (class "Default")
      (node (ref "C2") (pin "1") (pinfunction "1_1") (pintype "passive"))
      (node (ref "R1") (pin "1") (pinfunction "1_1") (pintype "passive"))
    )
    (net (code "29") (name "Net-(C15-Pad1)") (class "Default")
      (node (ref "C15") (pin "1") (pinfunction "1_1") (pintype "passive"))
      (node (ref "R3") (pin "1") (pinfunction "1_1") (pintype "passive"))
    )
    (net (code "30") (name "Net-(D1-A)") (class "Default")
      (node (ref "D1") (pin "2") (pinfunction "A_2") (pintype "passive"))
      (node (ref "P12") (pin "1") (pinfunction "1_1") (pintype "passive"))
    )
    (net (code "31") (name "Net-(P5-Pad2)") (class "Default")
      (node (ref "P5") (pin "2") (pinfunction "2_2") (pintype "passive"))
      (node (ref "R12") (pin "2") (pinfunction "2_2") (pintype "passive"))
      (node (ref "SW1") (pin "1") (pinfunction "1_1") (pintype "passive"))
      (node (ref "SW1") (pin "2") (pinfunction "1_2") (pintype "passive"))
    )
    (net (code "32") (name "Net-(U1-BOOT)") (class "Default")
      (node (ref "C1") (pin "1") (pinfunction "1_1") (pintype "passive"))
      (node (ref "U1") (pin "1") (pinfunction "BOOT_1") (pintype "passive"))
    )
    (net (code "33") (name "Net-(U1-RT{slash}CLK)") (class "Default")
      (node (ref "R2") (pin "2") (pinfunction "2_2") (pintype "passive"))
      (node (ref "U1") (pin "5") (pinfunction "RT/CLK_5") (pintype "passive"))
    )
    (net (code "34") (name "Net-(U1-SS{slash}TR)") (class "Default")
      (node (ref "C13") (pin "1") (pinfunction "1_1") (pintype "passive"))
      (node (ref "U1") (pin "4") (pinfunction "SS/TR_4") (pintype "passive"))
    )
    (net (code "35") (name "Net-(U2A-PB2-BOOT1(PB2))") (class "Default")
      (node (ref "R6") (pin "1") (pinfunction "1_1") (pintype "passive"))
      (node (ref "U2") (pin "28") (pinfunction "PB2-BOOT1(PB2)_28") (pintype "bidirectional"))
    )
    (net (code "36") (name "Net-(U2A-PC0)") (class "Default")
      (node (ref "R9") (pin "2") (pinfunction "2_2") (pintype "passive"))
      (node (ref "U2") (pin "8") (pinfunction "PC0_8") (pintype "bidirectional"))
    )
    (net (code "37") (name "Net-(U2A-PC1)") (class "Default")
      (node (ref "R11") (pin "2") (pinfunction "2_2") (pintype "passive"))
      (node (ref "U2") (pin "9") (pinfunction "PC1_9") (pintype "bidirectional"))
    )
    (net (code "38") (name "Net-(U2A-PC2)") (class "Default")
      (node (ref "R13") (pin "2") (pinfunction "2_2") (pintype "passive"))
      (node (ref "U2") (pin "10") (pinfunction "PC2_10") (pintype "bidirectional"))
    )
    (net (code "39") (name "Net-(U2A-PH0-OSC_IN(PH0))") (class "Default")
      (node (ref "C20") (pin "2") (pinfunction "2_2") (pintype "passive"))
      (node (ref "R10") (pin "2") (pinfunction "2_2") (pintype "passive"))
      (node (ref "U2") (pin "5") (pinfunction "PH0-OSC_IN(PH0)_5") (pintype "bidirectional"))
      (node (ref "X1") (pin "3") (pinfunction "OSC2_3") (pintype "passive"))
    )
    (net (code "40") (name "Net-(U2A-PH1-OSC_OUT(PH1))") (class "Default")
      (node (ref "C21") (pin "1") (pinfunction "1_1") (pintype "passive"))
      (node (ref "R10") (pin "1") (pinfunction "1_1") (pintype "passive"))
      (node (ref "U2") (pin "6") (pinfunction "PH1-OSC_OUT(PH1)_6") (pintype "bidirectional"))
      (node (ref "X1") (pin "1") (pinfunction "OSC1_1") (pintype "passive"))
    )
    (net (code "41") (name "Net-(U2A-VCAP_1)") (class "Default")
      (node (ref "C27") (pin "1") (pinfunction "1_1") (pintype "passive"))
      (node (ref "U2") (pin "31") (pinfunction "VCAP_1_31") (pintype "power_in"))
    )
    (net (code "42") (name "Net-(U2A-VCAP_2)") (class "Default")
      (node (ref "C26") (pin "1") (pinfunction "1_1") (pintype "passive"))
      (node (ref "U2") (pin "47") (pinfunction "VCAP_2_47") (pintype "power_in"))
    )
    (net (code "43") (name "Net-(U3-IN)") (class "Default")
      (node (ref "C16") (pin "1") (pinfunction "1_1") (pintype "passive"))
      (node (ref "C17") (pin "1") (pinfunction "1_1") (pintype "passive"))
      (node (ref "R23") (pin "2") (pinfunction "2_2") (pintype "passive"))
      (node (ref "U3") (pin "3") (pinfunction "IN_3") (pintype "power_in"))
    )
    (net (code "44") (name "Net-(U4-C1+)") (class "Default")
      (node (ref "C24") (pin "2") (pinfunction "2_2") (pintype "passive"))
      (node (ref "U4") (pin "1") (pinfunction "C1+_1") (pintype "passive"))
    )
    (net (code "45") (name "Net-(U4-C1-)") (class "Default")
      (node (ref "C24") (pin "1") (pinfunction "1_1") (pintype "passive"))
      (node (ref "U4") (pin "3") (pinfunction "C1-_3") (pintype "passive"))
    )
    (net (code "46") (name "Net-(U4-C2+)") (class "Default")
      (node (ref "C28") (pin "2") (pinfunction "2_2") (pintype "passive"))
      (node (ref "U4") (pin "4") (pinfunction "C2+_4") (pintype "passive"))
    )
    (net (code "47") (name "Net-(U4-C2-)") (class "Default")
      (node (ref "C28") (pin "1") (pinfunction "1_1") (pintype "passive"))
      (node (ref "U4") (pin "5") (pinfunction "C2-_5") (pintype "passive"))
    )
    (net (code "48") (name "Net-(U4-VS+)") (class "Default")
      (node (ref "C29") (pin "2") (pinfunction "2_2") (pintype "passive"))
      (node (ref "U4") (pin "2") (pinfunction "VS+_2") (pintype "passive"))
    )
    (net (code "49") (name "Net-(U4-VS-)") (class "Default")
      (node (ref "C30") (pin "2") (pinfunction "2_2") (pintype "passive"))
      (node (ref "U4") (pin "6") (pinfunction "VS-_6") (pintype "passive"))
    )
    (net (code "50") (name "unconnected-(P7-Pad3)") (class "Default")
      (node (ref "P7") (pin "3") (pinfunction "3_3") (pintype "passive+no_connect"))
    )
    (net (code "51") (name "unconnected-(P7-Pad4)") (class "Default")
      (node (ref "P7") (pin "4") (pinfunction "4_4") (pintype "passive+no_connect"))
    )
    (net (code "52") (name "unconnected-(P7-Pad5)") (class "Default")
      (node (ref "P7") (pin "5") (pinfunction "5_5") (pintype "passive+no_connect"))
    )
    (net (code "53") (name "unconnected-(P7-Pad6)") (class "Default")
      (node (ref "P7") (pin "6") (pinfunction "6_6") (pintype "passive+no_connect"))
    )
    (net (code "54") (name "unconnected-(U1-EN-Pad3)") (class "Default")
      (node (ref "U1") (pin "3") (pinfunction "EN_3") (pintype "passive+no_connect"))
    )
    (net (code "55") (name "unconnected-(U1-PWRGD-Pad10)") (class "Default")
      (node (ref "U1") (pin "10") (pinfunction "PWRGD_10") (pintype "passive"))
    )
    (net (code "56") (name "unconnected-(U2A-PA0-WKUP(PA0)-Pad14)") (class "Default")
      (node (ref "U2") (pin "14") (pinfunction "PA0-WKUP(PA0)_14") (pintype "bidirectional+no_connect"))
    )
    (net (code "57") (name "unconnected-(U2A-PA1-Pad15)") (class "Default")
      (node (ref "U2") (pin "15") (pinfunction "PA1_15") (pintype "bidirectional+no_connect"))
    )
    (net (code "58") (name "unconnected-(U2A-PA5-Pad21)") (class "Default")
      (node (ref "U2") (pin "21") (pinfunction "PA5_21") (pintype "bidirectional+no_connect"))
    )
    (net (code "59") (name "unconnected-(U2A-PA6-Pad22)") (class "Default")
      (node (ref "U2") (pin "22") (pinfunction "PA6_22") (pintype "bidirectional+no_connect"))
    )
    (net (code "60") (name "unconnected-(U2A-PA7-Pad23)") (class "Default")
      (node (ref "U2") (pin "23") (pinfunction "PA7_23") (pintype "bidirectional+no_connect"))
    )
    (net (code "61") (name "unconnected-(U2A-PA8-Pad41)") (class "Default")
      (node (ref "U2") (pin "41") (pinfunction "PA8_41") (pintype "bidirectional+no_connect"))
    )
    (net (code "62") (name "unconnected-(U2A-PA11-Pad44)") (class "Default")
      (node (ref "U2") (pin "44") (pinfunction "PA11_44") (pintype "bidirectional+no_connect"))
    )
    (net (code "63") (name "unconnected-(U2A-PA12-Pad45)") (class "Default")
      (node (ref "U2") (pin "45") (pinfunction "PA12_45") (pintype "bidirectional+no_connect"))
    )
    (net (code "64") (name "unconnected-(U2A-PA15(JTDI)-Pad50)") (class "Default")
      (node (ref "U2") (pin "50") (pinfunction "PA15(JTDI)_50") (pintype "bidirectional+no_connect"))
    )
    (net (code "65") (name "unconnected-(U2A-PB0-Pad26)") (class "Default")
      (node (ref "U2") (pin "26") (pinfunction "PB0_26") (pintype "bidirectional+no_connect"))
    )
    (net (code "66") (name "unconnected-(U2A-PB1-Pad27)") (class "Default")
      (node (ref "U2") (pin "27") (pinfunction "PB1_27") (pintype "bidirectional+no_connect"))
    )
    (net (code "67") (name "unconnected-(U2A-PB3(JTDO{slash}TRACESWO)-Pad55)") (class "Default")
      (node (ref "U2") (pin "55") (pinfunction "PB3(JTDO/TRACESWO)_55") (pintype "bidirectional+no_connect"))
    )
    (net (code "68") (name "unconnected-(U2A-PB4(NJTRST)-Pad56)") (class "Default")
      (node (ref "U2") (pin "56") (pinfunction "PB4(NJTRST)_56") (pintype "bidirectional+no_connect"))
    )
    (net (code "69") (name "unconnected-(U2A-PB5-Pad57)") (class "Default")
      (node (ref "U2") (pin "57") (pinfunction "PB5_57") (pintype "bidirectional+no_connect"))
    )
    (net (code "70") (name "unconnected-(U2A-PB8-Pad61)") (class "Default")
      (node (ref "U2") (pin "61") (pinfunction "PB8_61") (pintype "bidirectional+no_connect"))
    )
    (net (code "71") (name "unconnected-(U2A-PB9-Pad62)") (class "Default")
      (node (ref "U2") (pin "62") (pinfunction "PB9_62") (pintype "bidirectional+no_connect"))
    )
    (net (code "72") (name "unconnected-(U2A-PB10-Pad29)") (class "Default")
      (node (ref "U2") (pin "29") (pinfunction "PB10_29") (pintype "bidirectional+no_connect"))
    )
    (net (code "73") (name "unconnected-(U2A-PB11-Pad30)") (class "Default")
      (node (ref "U2") (pin "30") (pinfunction "PB11_30") (pintype "bidirectional+no_connect"))
    )
    (net (code "74") (name "unconnected-(U2A-PB12-Pad33)") (class "Default")
      (node (ref "U2") (pin "33") (pinfunction "PB12_33") (pintype "bidirectional+no_connect"))
    )
    (net (code "75") (name "unconnected-(U2A-PB13-Pad34)") (class "Default")
      (node (ref "U2") (pin "34") (pinfunction "PB13_34") (pintype "bidirectional+no_connect"))
    )
    (net (code "76") (name "unconnected-(U2A-PB14-Pad35)") (class "Default")
      (node (ref "U2") (pin "35") (pinfunction "PB14_35") (pintype "bidirectional+no_connect"))
    )
    (net (code "77") (name "unconnected-(U2A-PB15-Pad36)") (class "Default")
      (node (ref "U2") (pin "36") (pinfunction "PB15_36") (pintype "bidirectional+no_connect"))
    )
    (net (code "78") (name "unconnected-(U2A-PC3-Pad11)") (class "Default")
      (node (ref "U2") (pin "11") (pinfunction "PC3_11") (pintype "bidirectional+no_connect"))
    )
    (net (code "79") (name "unconnected-(U2A-PC4-Pad24)") (class "Default")
      (node (ref "U2") (pin "24") (pinfunction "PC4_24") (pintype "bidirectional+no_connect"))
    )
    (net (code "80") (name "unconnected-(U2A-PC5-Pad25)") (class "Default")
      (node (ref "U2") (pin "25") (pinfunction "PC5_25") (pintype "bidirectional+no_connect"))
    )
    (net (code "81") (name "unconnected-(U2A-PC6-Pad37)") (class "Default")
      (node (ref "U2") (pin "37") (pinfunction "PC6_37") (pintype "bidirectional+no_connect"))
    )
    (net (code "82") (name "unconnected-(U2A-PC7-Pad38)") (class "Default")
      (node (ref "U2") (pin "38") (pinfunction "PC7_38") (pintype "bidirectional+no_connect"))
    )
    (net (code "83") (name "unconnected-(U2A-PC8-Pad39)") (class "Default")
      (node (ref "U2") (pin "39") (pinfunction "PC8_39") (pintype "bidirectional+no_connect"))
    )
    (net (code "84") (name "unconnected-(U2A-PC9-Pad40)") (class "Default")
      (node (ref "U2") (pin "40") (pinfunction "PC9_40") (pintype "bidirectional+no_connect"))
    )
    (net (code "85") (name "unconnected-(U2A-PC12-Pad53)") (class "Default")
      (node (ref "U2") (pin "53") (pinfunction "PC12_53") (pintype "bidirectional+no_connect"))
    )
    (net (code "86") (name "unconnected-(U2A-PC13-Pad2)") (class "Default")
      (node (ref "U2") (pin "2") (pinfunction "PC13_2") (pintype "bidirectional+no_connect"))
    )
    (net (code "87") (name "unconnected-(U2A-PC14-OSC32_IN(PC14)-Pad3)") (class "Default")
      (node (ref "U2") (pin "3") (pinfunction "PC14-OSC32_IN(PC14)_3") (pintype "bidirectional+no_connect"))
    )
    (net (code "88") (name "unconnected-(U2A-PC15-OSC32_OUT(PC15)-Pad4)") (class "Default")
      (node (ref "U2") (pin "4") (pinfunction "PC15-OSC32_OUT(PC15)_4") (pintype "bidirectional+no_connect"))
    )
    (net (code "89") (name "unconnected-(U2A-PD2-Pad54)") (class "Default")
      (node (ref "U2") (pin "54") (pinfunction "PD2_54") (pintype "bidirectional"))
    )
    (net (code "90") (name "unconnected-(U4-R1IN-Pad13)") (class "Default")
      (node (ref "U4") (pin "13") (pinfunction "R1IN_13") (pintype "passive+no_connect"))
    )
    (net (code "91") (name "unconnected-(U4-R1OUT-Pad12)") (class "Default")
      (node (ref "U4") (pin "12") (pinfunction "R1OUT_12") (pintype "passive+no_connect"))
    )
    (net (code "92") (name "unconnected-(U4-T1IN-Pad11)") (class "Default")
      (node (ref "U4") (pin "11") (pinfunction "T1IN_11") (pintype "passive+no_connect"))
    )
    (net (code "93") (name "unconnected-(U4-T1OUT-Pad14)") (class "Default")
      (node (ref "U4") (pin "14") (pinfunction "T1OUT_14") (pintype "passive+no_connect"))
    )
  )
)
